# PiCarHat_Master_V4.net
KiCad netlist of a schematic drawn in Altium Designer
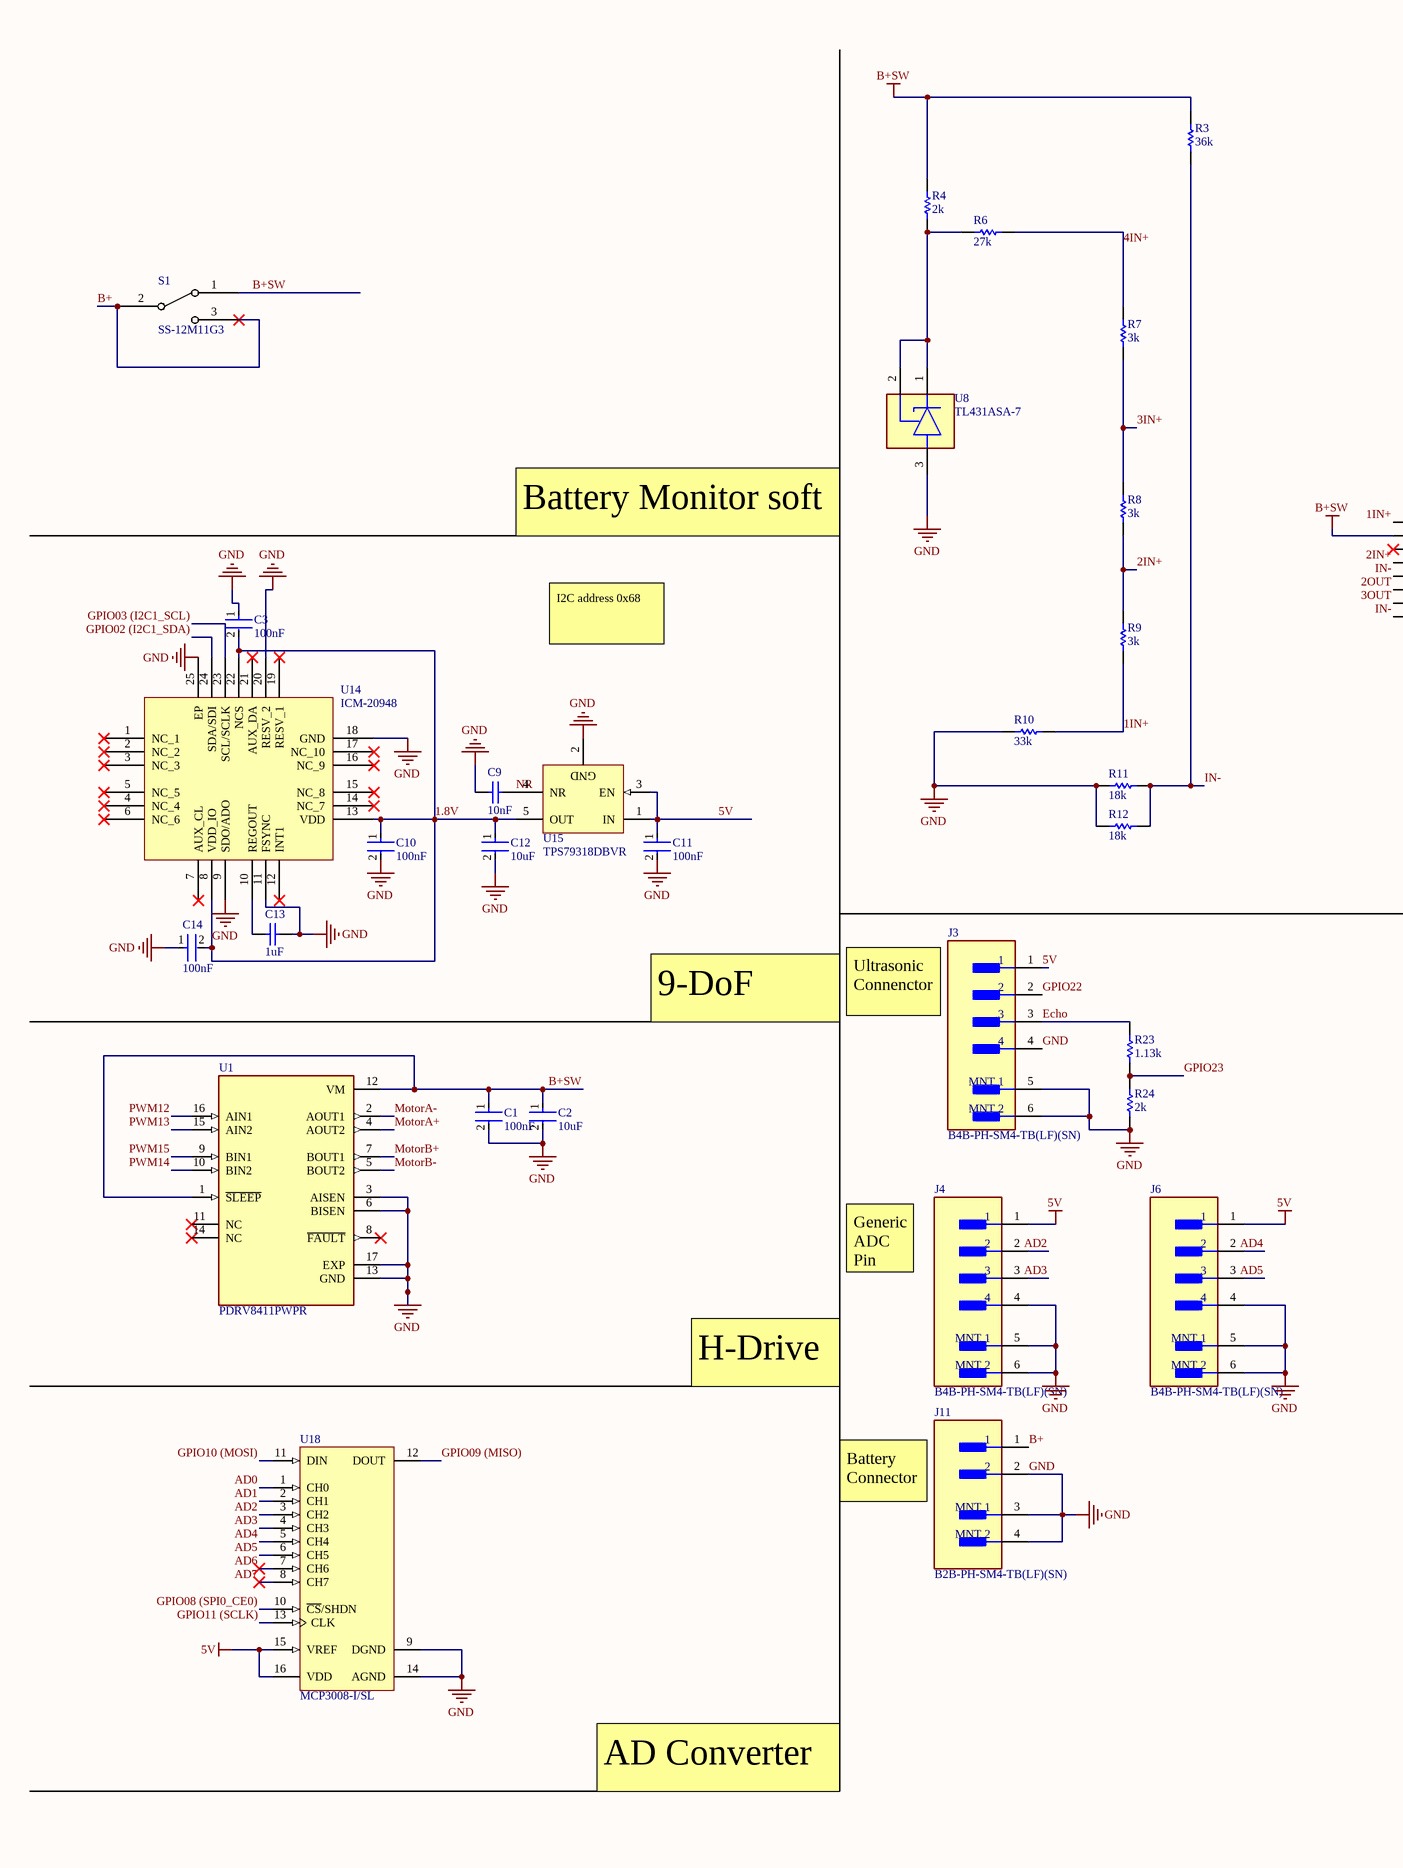
[diagram p0: PiCarHat_Master_V4.SchDoc, left]
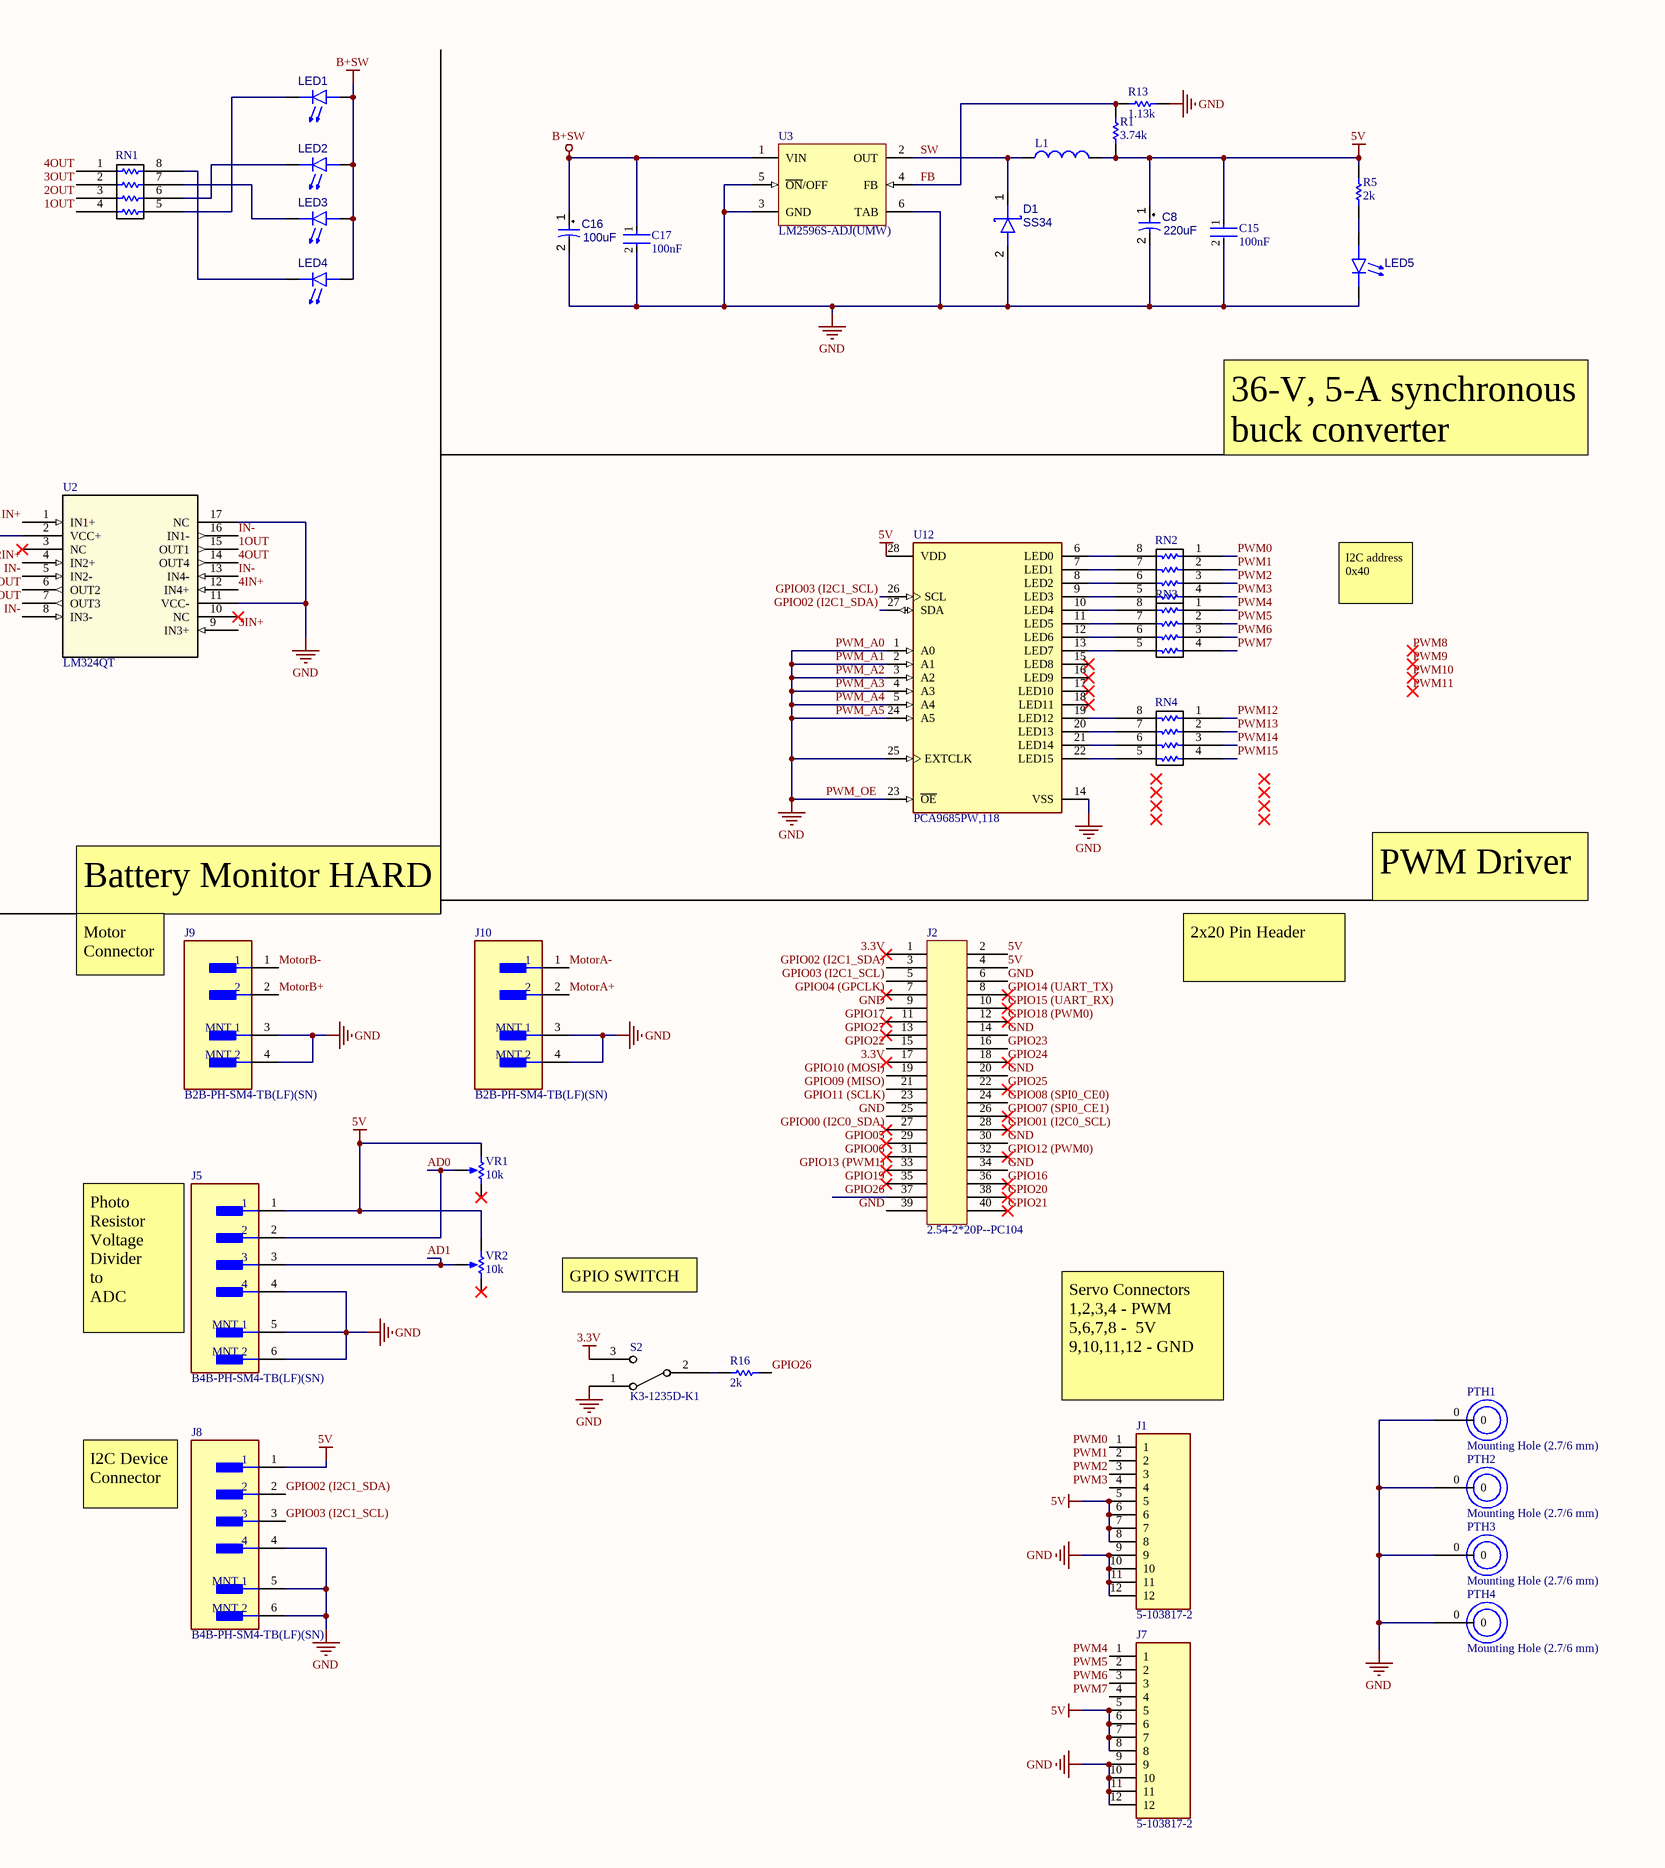
[diagram p1: PiCarHat_Master_V4.SchDoc, right]

(export (version "E")
  (design (tool "Eeschema 10.0.6"))
  (components
    (comp (ref "C1")
      (value "100nF")
      (footprint "FP-CC0805-0_85-IPC_B")
      (description "50V 100nF X7R ±10% 0805 Multilayer Ceramic Capacitors MLCC - SMD/SMT ROHS")
      (fields (field (name "TOLERANCE") "0.1") (field (name "PART NUMBER") "CC0805KRX7R9BB104"))
      (libsource (lib "Altium Content Vault") (part "11868f565c42a9108669ba33697ecf6"))
    )
    (comp (ref "C2")
      (value "10uF")
      (footprint "FP-GRM21B-0_15-MFG")
      (description "25V 10uF X5R ±10% 0805 Multilayer Ceramic Capacitors MLCC - SMD/SMT ROHS")
      (fields (field (name "VOLTAGE") "25V") (field (name "TOLERANCE") "10%"))
      (libsource (lib "Altium Content Vault") (part "b4654b650e69147ec39a6b967a45e02"))
    )
    (comp (ref "C3")
      (value "100nF")
      (footprint "FP-CC0805-0_85-IPC_B")
      (description "50V 100nF X7R ±10% 0805 Multilayer Ceramic Capacitors MLCC - SMD/SMT ROHS")
      (fields (field (name "TOLERANCE") "0.1") (field (name "PART NUMBER") "CC0805KRX7R9BB104"))
      (libsource (lib "Altium Content Vault") (part "11868f565c42a9108669ba33697ecf6"))
    )
    (comp (ref "C8")
      (value "220uF")
      (footprint "RVT1A221M0605-Footprint-1")
      (description "220uF 10V 90mA@120Hz ±20% SMD, D6.3xL5.4mm Aluminum Electrolytic Capacitors - SMD ROHS")
      (fields (field (name "JLCPCB PART #") "C3345") (field (name "PART NUMBER") "RVT1A221M0605"))
      (libsource (lib "Ethan Morton Personal") (part "CAP-NP-2"))
    )
    (comp (ref "C9")
      (value "10nF")
      (footprint "CAPC2013X100X50NL20T25")
      (description "50V 10nF X7R ±10% 0805 Multilayer Ceramic Capacitors MLCC - SMD/SMT ROHS")
      (fields (field (name "PART NUMBER") "C0805F103K5RACTU") (field (name "MANUFACTURER") "Kemet"))
      (libsource (lib "Altium Content Vault") (part "CAP"))
    )
    (comp (ref "C10")
      (value "100nF")
      (footprint "FP-CC0805-0_85-IPC_B")
      (description "50V 100nF X7R ±10% 0805 Multilayer Ceramic Capacitors MLCC - SMD/SMT ROHS")
      (fields (field (name "TOLERANCE") "0.1") (field (name "PART NUMBER") "CC0805KRX7R9BB104"))
      (libsource (lib "Altium Content Vault") (part "11868f565c42a9108669ba33697ecf6"))
    )
    (comp (ref "C11")
      (value "100nF")
      (footprint "FP-CC0805-0_85-IPC_B")
      (description "50V 100nF X7R ±10% 0805 Multilayer Ceramic Capacitors MLCC - SMD/SMT ROHS")
      (fields (field (name "TOLERANCE") "0.1") (field (name "PART NUMBER") "CC0805KRX7R9BB104"))
      (libsource (lib "Altium Content Vault") (part "11868f565c42a9108669ba33697ecf6"))
    )
    (comp (ref "C12")
      (value "10uF")
      (footprint "FP-GRM21B-0_15-MFG")
      (description "25V 10uF X5R ±10% 0805 Multilayer Ceramic Capacitors MLCC - SMD/SMT ROHS")
      (fields (field (name "VOLTAGE") "25V") (field (name "TOLERANCE") "10%"))
      (libsource (lib "Altium Content Vault") (part "b4654b650e69147ec39a6b967a45e02"))
    )
    (comp (ref "C13")
      (value "1uF")
      (footprint "CAPC2013X140X50LL20T25")
      (description "50V 1uF X7R ±10% 0805 Multilayer Ceramic Capacitors MLCC - SMD/SMT ROHS")
      (fields (field (name "PART NUMBER") "C0805C105K3RACTU") (field (name "MANUFACTURER") "Kemet"))
      (libsource (lib "Altium Content Vault") (part "CAP"))
    )
    (comp (ref "C14")
      (value "100nF")
      (footprint "FP-CC0805-0_85-IPC_B")
      (description "50V 100nF X7R ±10% 0805 Multilayer Ceramic Capacitors MLCC - SMD/SMT ROHS")
      (fields (field (name "TOLERANCE") "0.1") (field (name "PART NUMBER") "CC0805KRX7R9BB104"))
      (libsource (lib "Altium Content Vault") (part "11868f565c42a9108669ba33697ecf6"))
    )
    (comp (ref "C15")
      (value "100nF")
      (footprint "FP-CC0805-0_85-IPC_B")
      (description "50V 100nF X7R ±10% 0805 Multilayer Ceramic Capacitors MLCC - SMD/SMT ROHS")
      (fields (field (name "TOLERANCE") "0.1") (field (name "PART NUMBER") "CC0805KRX7R9BB104"))
      (libsource (lib "Altium Content Vault") (part "11868f565c42a9108669ba33697ecf6"))
    )
    (comp (ref "C16")
      (value "100uF")
      (footprint "RVT1C101M0605-Footprint-1")
      (description "100uF 16V 63mA@120Hz ±20% SMD, D6.3xL5.4mm Aluminum Electrolytic Capacitors - SMD ROHS")
      (fields (field (name "PART NUMBER") "RVT1C101M0605") (field (name "JLCPCB PART #") "C37308"))
      (libsource (lib "Ethan Morton Personal") (part "Copy of CAP-NP-2"))
    )
    (comp (ref "C17")
      (value "100nF")
      (footprint "FP-CC0805-0_85-IPC_B")
      (description "50V 100nF X7R ±10% 0805 Multilayer Ceramic Capacitors MLCC - SMD/SMT ROHS")
      (fields (field (name "TOLERANCE") "0.1") (field (name "PART NUMBER") "CC0805KRX7R9BB104"))
      (libsource (lib "Altium Content Vault") (part "11868f565c42a9108669ba33697ecf6"))
    )
    (comp (ref "D1")
      (value "SS34")
      (footprint "SS34-Footprint-1")
      (description "40V Independent Type 3A 550mV@3A SMA(DO-214AC) Schottky Diodes ROHS")
      (fields (field (name "JLCPCB PART #") "C8678"))
      (libsource (lib "Ethan Morton Personal") (part "Copy of DIODE-2"))
    )
    (comp (ref "J1")
      (value "5-103817-2")
      (footprint "TE_5-103817-2")
      (fields
        (field (name "MF") "TE Connectivity")
        (field (name "PART NUMBER") "TSW-104-07-L-T")
        (field (name "JLCPCB PART #") "C32713291")
      )
      (libsource (lib "Ethan Morton Personal") (part "5-103817-2"))
    )
    (comp (ref "J2")
      (value "2.54-2*20P--PC104")
      (footprint "New footprint 1")
      (description "2.54mm 2.54mm Double Row 40P Brass Direct Insert 2x20P Plugin,P=2.54mm Female Headers ROHS")
      (fields (field (name "PART NUMBER") "2.54-2*20P母长PC104") (field (name "JLCPCB PART #") "C35165"))
      (libsource (lib "Ethan Morton Personal") (part "2x20 GPIO Header"))
    )
    (comp (ref "J3")
      (value "B4B-PH-SM4-TB(LF)(SN)")
      (footprint "FP-B4B-PH-SM4-TB-MFG")
      (description "2.0mm pitch/Disconnectable Insulation displacement and Crimp style connectors")
      (fields (field (name "JLCPCB PART #") "C160354"))
      (libsource (lib "Ethan Morton Personal") (part "f4320a1371cd6270e33bce1916c33c0"))
    )
    (comp (ref "J4")
      (value "B4B-PH-SM4-TB(LF)(SN)")
      (footprint "FP-B4B-PH-SM4-TB-MFG")
      (description "2.0mm pitch/Disconnectable Insulation displacement and Crimp style connectors")
      (fields (field (name "JLCPCB PART #") "C160354"))
      (libsource (lib "Ethan Morton Personal") (part "f4320a1371cd6270e33bce1916c33c0"))
    )
    (comp (ref "J5")
      (value "B4B-PH-SM4-TB(LF)(SN)")
      (footprint "FP-B4B-PH-SM4-TB-MFG")
      (description "2.0mm pitch/Disconnectable Insulation displacement and Crimp style connectors")
      (fields (field (name "JLCPCB PART #") "C160354"))
      (libsource (lib "Ethan Morton Personal") (part "f4320a1371cd6270e33bce1916c33c0"))
    )
    (comp (ref "J6")
      (value "B4B-PH-SM4-TB(LF)(SN)")
      (footprint "FP-B4B-PH-SM4-TB-MFG")
      (description "2.0mm pitch/Disconnectable Insulation displacement and Crimp style connectors")
      (fields (field (name "JLCPCB PART #") "C160354"))
      (libsource (lib "Ethan Morton Personal") (part "f4320a1371cd6270e33bce1916c33c0"))
    )
    (comp (ref "J7")
      (value "5-103817-2")
      (footprint "TE_5-103817-2")
      (fields
        (field (name "PART NUMBER") "TSW-104-07-L-T")
        (field (name "MF") "TE Connectivity")
        (field (name "JLCPCB PART #") "C32713291")
      )
      (libsource (lib "Ethan Morton Personal") (part "5-103817-2"))
    )
    (comp (ref "J8")
      (value "B4B-PH-SM4-TB(LF)(SN)")
      (footprint "FP-B4B-PH-SM4-TB-MFG")
      (description "2.0mm pitch/Disconnectable Insulation displacement and Crimp style connectors")
      (fields (field (name "JLCPCB PART #") "C160354"))
      (libsource (lib "Ethan Morton Personal") (part "f4320a1371cd6270e33bce1916c33c0"))
    )
    (comp (ref "J9")
      (value "B2B-PH-SM4-TB(LF)(SN)")
      (footprint "FP-B2B-PH-SM4-TB_LF_SN-MFG")
      (fields (field (name "PART NUMBER") "B2B-PH-SM4-TB") (field (name "JLCPCB PART #") "C160352"))
      (libsource (lib "Ethan Morton Personal") (part "56ec3178a87b3978bdc1b3682cd516a"))
    )
    (comp (ref "J10")
      (value "B2B-PH-SM4-TB(LF)(SN)")
      (footprint "FP-B2B-PH-SM4-TB_LF_SN-MFG")
      (fields (field (name "PART NUMBER") "B2B-PH-SM4-TB") (field (name "JLCPCB PART #") "C160352"))
      (libsource (lib "Ethan Morton Personal") (part "56ec3178a87b3978bdc1b3682cd516a"))
    )
    (comp (ref "J11")
      (value "B2B-PH-SM4-TB(LF)(SN)")
      (footprint "FP-B2B-PH-SM4-TB_LF_SN-MFG")
      (fields (field (name "PART NUMBER") "B2B-PH-SM4-TB") (field (name "JLCPCB PART #") "C160352"))
      (libsource (lib "Ethan Morton Personal") (part "56ec3178a87b3978bdc1b3682cd516a"))
    )
    (comp (ref "L1")
      (value "FXL1050-470-M")
      (footprint "FXL1050-470-M-Footprint-1")
      (description "3.7A 47uH Integrated molded inductor ±20% 4.5A SMD,10x11.5mm Power Inductors ROHS")
      (fields (field (name "JLCPCB PART #") "C5359268"))
      (libsource (lib "Ethan Morton Personal") (part "IND-2"))
    )
    (comp (ref "LED1")
      (value "KT-0603R")
      (footprint "XL-1608SURC-06-Footprint-1")
      (description "-40℃~+85℃ Red 0603 LED Indication - Discrete ROHS")
      (fields (field (name "JLCPCB PART #") "C2286"))
      (libsource (lib "Ethan Morton Personal") (part "Copy of DIODE-LED-2"))
    )
    (comp (ref "LED2")
      (value "KT-0603R")
      (footprint "XL-1608SURC-06-Footprint-1")
      (description "-40℃~+85℃ Red 0603 LED Indication - Discrete ROHS")
      (fields (field (name "JLCPCB PART #") "C2286"))
      (libsource (lib "Ethan Morton Personal") (part "Copy of DIODE-LED-2"))
    )
    (comp (ref "LED3")
      (value "KT-0603R")
      (footprint "XL-1608SURC-06-Footprint-1")
      (description "-40℃~+85℃ Red 0603 LED Indication - Discrete ROHS")
      (fields (field (name "JLCPCB PART #") "C2286"))
      (libsource (lib "Ethan Morton Personal") (part "Copy of DIODE-LED-2"))
    )
    (comp (ref "LED4")
      (value "KT-0603R")
      (footprint "XL-1608SURC-06-Footprint-1")
      (description "-40℃~+85℃ Red 0603 LED Indication - Discrete ROHS")
      (fields (field (name "JLCPCB PART #") "C2286"))
      (libsource (lib "Ethan Morton Personal") (part "Copy of DIODE-LED-2"))
    )
    (comp (ref "LED5")
      (value "KT-0603R")
      (footprint "XL-1608SURC-06-Footprint-1")
      (description "-40℃~+85℃ Red 0603 LED Indication - Discrete ROHS")
      (fields (field (name "JLCPCB PART #") "C2286"))
      (libsource (lib "Ethan Morton Personal") (part "Copy of DIODE-LED-2"))
    )
    (comp (ref "PTH1")
      (value "Mounting Hole (2.7/6 mm)")
      (footprint "New footprint 1")
      (description "DO NOT PLACE")
      (libsource (lib "Ethan Morton Personal") (part "Mounting Hole (2.7/6 mm)"))
    )
    (comp (ref "PTH2")
      (value "Mounting Hole (2.7/6 mm)")
      (footprint "New footprint 1")
      (description "DO NOT PLACE")
      (libsource (lib "Ethan Morton Personal") (part "Mounting Hole (2.7/6 mm)"))
    )
    (comp (ref "PTH3")
      (value "Mounting Hole (2.7/6 mm)")
      (footprint "New footprint 1")
      (description "DO NOT PLACE")
      (libsource (lib "Ethan Morton Personal") (part "Mounting Hole (2.7/6 mm)"))
    )
    (comp (ref "PTH4")
      (value "Mounting Hole (2.7/6 mm)")
      (footprint "New footprint 1")
      (description "DO NOT PLACE")
      (libsource (lib "Ethan Morton Personal") (part "Mounting Hole (2.7/6 mm)"))
    )
    (comp (ref "R1")
      (value "3.74k")
      (footprint "RESC1608X55X30LL15T15")
      (description "100mW Thick Film Resistors 75V ±100ppm/℃ ±1% 3.74kΩ 0603 Chip Resistor - Surface Mount ROHS")
      (fields (field (name "PART NUMBER") "ERJ-3EKF3741V") (field (name "MANUFACTURER") "Panasonic"))
      (libsource (lib "Altium Content Vault") (part "RES"))
    )
    (comp (ref "R3")
      (value "36k")
      (footprint "RESC1608X55X30LL20T20")
      (description "100mW Thick Film Resistors 75V ±100ppm/℃ ±1% 36kΩ 0603 Chip Resistor - Surface Mount ROHS")
      (fields (field (name "MANUFACTURER") "Panasonic") (field (name "PART NUMBER") "ERA3AEB363V"))
      (libsource (lib "Altium Content Vault") (part "RES"))
    )
    (comp (ref "R4")
      (value "2k")
      (footprint "RESC1608X55X25LL10T15")
      (description "100mW Thick Film Resistors 75V ±100ppm/℃ ±1% 2kΩ 0603 Chip Resistor - Surface Mount ROHS")
      (fields (field (name "TOLERANCE") "±1%") (field (name "MANUFACTURER") "Yageo"))
      (libsource (lib "") (part "RES-2_1"))
    )
    (comp (ref "R5")
      (value "2k")
      (footprint "RESC1608X55X25LL10T15")
      (description "100mW Thick Film Resistors 75V ±100ppm/℃ ±1% 2kΩ 0603 Chip Resistor - Surface Mount ROHS")
      (fields (field (name "TOLERANCE") "±1%") (field (name "MANUFACTURER") "Yageo"))
      (libsource (lib "") (part "RES-2_1"))
    )
    (comp (ref "R6")
      (value "27k")
      (footprint "RESC1608X55X25LL10T15")
      (description "100mW Thick Film Resistors 75V ±100ppm/℃ ±1% 27kΩ 0603 Chip Resistor - Surface Mount ROHS")
      (fields (field (name "MANUFACTURER") "Yageo") (field (name "TOLERANCE") "1%"))
      (libsource (lib "") (part "RES-2_1"))
    )
    (comp (ref "R7")
      (value "3k")
      (footprint "RESC1608X55X25LL10T15")
      (description "100mW Thick Film Resistors 75V ±100ppm/℃ ±1% 3kΩ 0603 Chip Resistor - Surface Mount ROHS")
      (fields (field (name "MANUFACTURER") "Yageo") (field (name "PART NUMBER") "RC0603FR-073KL"))
      (libsource (lib "Altium Content Vault") (part "RES"))
    )
    (comp (ref "R8")
      (value "3k")
      (footprint "RESC1608X55X25LL10T15")
      (description "100mW Thick Film Resistors 75V ±100ppm/℃ ±1% 3kΩ 0603 Chip Resistor - Surface Mount ROHS")
      (fields (field (name "MANUFACTURER") "Yageo") (field (name "PART NUMBER") "RC0603FR-073KL"))
      (libsource (lib "Altium Content Vault") (part "RES"))
    )
    (comp (ref "R9")
      (value "3k")
      (footprint "RESC1608X55X25LL10T15")
      (description "100mW Thick Film Resistors 75V ±100ppm/℃ ±1% 3kΩ 0603 Chip Resistor - Surface Mount ROHS")
      (fields (field (name "MANUFACTURER") "Yageo") (field (name "PART NUMBER") "RC0603FR-073KL"))
      (libsource (lib "Altium Content Vault") (part "RES"))
    )
    (comp (ref "R10")
      (value "33k")
      (footprint "RESC1608X55X25LL10T15")
      (description "100mW Thick Film Resistors 75V ±100ppm/℃ ±1% 33kΩ 0603 Chip Resistor - Surface Mount ROHS")
      (fields (field (name "TOLERANCE") "1%") (field (name "MANUFACTURER") "Yageo"))
      (libsource (lib "") (part "RES-2_1"))
    )
    (comp (ref "R11")
      (value "18k")
      (footprint "RESC1608X55X30LL15T15")
      (description "100mW Thick Film Resistors 75V ±100ppm/℃ ±1% 18kΩ 0603 Chip Resistor - Surface Mount ROHS")
      (fields (field (name "MANUFACTURER") "Panasonic") (field (name "PART NUMBER") "ERJ3EKF1802V"))
      (libsource (lib "Altium Content Vault") (part "RES-2"))
    )
    (comp (ref "R12")
      (value "18k")
      (footprint "RESC1608X55X30LL15T15")
      (description "100mW Thick Film Resistors 75V ±100ppm/℃ ±1% 18kΩ 0603 Chip Resistor - Surface Mount ROHS")
      (fields (field (name "MANUFACTURER") "Panasonic") (field (name "PART NUMBER") "ERJ3EKF1802V"))
      (libsource (lib "Altium Content Vault") (part "RES-2"))
    )
    (comp (ref "R13")
      (value "1.13k")
      (footprint "RESC1609X50X30LL10T20")
      (description "100mW Thick Film Resistors 75V ±100ppm/℃ ±1% 1.13kΩ 0603 Chip Resistor - Surface Mount ROHS")
      (fields (field (name "PART NUMBER") "CRCW06031K13FKEA") (field (name "MANUFACTURER") "Vishay Dale"))
      (libsource (lib "Altium Content Vault") (part "RES"))
    )
    (comp (ref "R16")
      (value "2k")
      (footprint "RESC1608X55X25LL10T15")
      (description "100mW Thick Film Resistors 75V ±100ppm/℃ ±1% 2kΩ 0603 Chip Resistor - Surface Mount ROHS")
      (fields (field (name "TOLERANCE") "±1%") (field (name "MANUFACTURER") "Yageo"))
      (libsource (lib "") (part "RES-2_1"))
    )
    (comp (ref "R23")
      (value "1.13k")
      (footprint "RESC1609X50X30LL10T20")
      (description "100mW Thick Film Resistors 75V ±100ppm/℃ ±1% 1.13kΩ 0603 Chip Resistor - Surface Mount ROHS")
      (fields (field (name "PART NUMBER") "CRCW06031K13FKEA") (field (name "MANUFACTURER") "Vishay Dale"))
      (libsource (lib "Altium Content Vault") (part "RES"))
    )
    (comp (ref "R24")
      (value "2k")
      (footprint "RESC1608X55X25LL10T15")
      (description "100mW Thick Film Resistors 75V ±100ppm/℃ ±1% 2kΩ 0603 Chip Resistor - Surface Mount ROHS")
      (fields (field (name "TOLERANCE") "±1%") (field (name "MANUFACTURER") "Yageo"))
      (libsource (lib "") (part "RES-2_1"))
    )
    (comp (ref "RN1")
      (value "4D03WGJ0103T5E")
      (footprint "4D03WGJ0103T5E-Footprint-1")
      (description "4 ±5% 10kΩ 62.5mW ±200ppm/℃ 0603x4 Resistor Networks, Arrays ROHS")
      (fields (field (name "JLCPCB PART #") "C29718"))
      (libsource (lib "Ethan Morton Personal") (part "10k Resistor Network"))
    )
    (comp (ref "RN2")
      (value "4D03WGJ0101T5E")
      (footprint "4D03WGJ0101T5E-Footprint-1")
      (description "4 ±5% 100Ω 62.5mW ±200ppm/℃ 0603x4 Resistor Networks, Arrays ROHS")
      (fields (field (name "JLCPCB PART #") "C25506"))
      (libsource (lib "Ethan Morton Personal") (part "4D03WGJ0101T5E-Symbol-1"))
    )
    (comp (ref "RN3")
      (value "4D03WGJ0101T5E")
      (footprint "4D03WGJ0101T5E-Footprint-1")
      (description "4 ±5% 100Ω 62.5mW ±200ppm/℃ 0603x4 Resistor Networks, Arrays ROHS")
      (fields (field (name "JLCPCB PART #") "C25506"))
      (libsource (lib "Ethan Morton Personal") (part "4D03WGJ0101T5E-Symbol-1"))
    )
    (comp (ref "RN4")
      (value "4D03WGJ0101T5E")
      (footprint "4D03WGJ0101T5E-Footprint-1")
      (description "4 ±5% 100Ω 62.5mW ±200ppm/℃ 0603x4 Resistor Networks, Arrays ROHS")
      (fields (field (name "JLCPCB PART #") "C25506"))
      (libsource (lib "Ethan Morton Personal") (part "4D03WGJ0101T5E-Symbol-1"))
    )
    (comp (ref "S1")
      (value "SS-12M11G3")
      (footprint "SS-12M11G5-Footprint-1")
      (fields (field (name "JLCPCB PART #") "C2879832"))
      (libsource (lib "Ethan Morton Personal") (part "SS-12M11G5-Symbol-1"))
    )
    (comp (ref "S2")
      (value "K3-1235D-K1")
      (footprint "K3-1235D-K1-Footprint-1")
      (fields (field (name "JLCPCB PART #") "C145860"))
      (libsource (lib "Ethan Morton Personal") (part "K3-1235D-K1-Symbol-1"))
    )
    (comp (ref "U1")
      (value "PDRV8411PWPR")
      (footprint "PWP0016C-IPC_B")
      (description "1.65-V to 11-V, 4-A, dual H-bridge motor driver with current regulation 16-HTSSOP -40 to 125")
      (fields (field (name "JLCPCB PART #") "C18212622"))
      (libsource (lib "Ethan Morton Personal") (part "PDRV8411PWPR-Symbol-1"))
    )
    (comp (ref "U2")
      (value "LM324QT")
      (footprint "LM324QT-Footprint-1")
      (description "Operational Amplifier, 4 Func, 9000uV Offset-Max, BIPolar, PQCC16")
      (fields (field (name "JLCPCB PART #") "C183029"))
      (libsource (lib "Ethan Morton Personal") (part "LM324QT-Symbol-1"))
    )
    (comp (ref "U3")
      (value "LM2596S-ADJ(UMW)")
      (footprint "TS5B_L")
      (description "Step-down type Adjustable 40V 1.2V~37V 3A TO-263-5 DC-DC Converters ROHS")
      (fields (field (name "MANUFACTURER") "National Semiconductor") (field (name "JLCPCB PART #") "C347423"))
      (libsource (lib "Altium Content Vault") (part "PM-REG-LM2575HVS-12"))
    )
    (comp (ref "U8")
      (value "TL431ASA-7")
      (footprint "FP-SOT23-MFG")
      (description "2.495V~36V ±1% 100mA Adjustable SOT-23 Voltage Reference ROHS")
      (fields
        (field (name "OCTOPART") "https://octopart.com/tl431asa-7-diodes+inc.-18832779")
        (field (name "MANUFACTURER") "DIODES INC.")
      )
      (libsource (lib "Altium Content Vault") (part "bb7a1bf3cd7629b94a2ffd22ed0b9f9"))
    )
    (comp (ref "U12")
      (value "PCA9685PW,118")
      (footprint "FP-SOT361-1-IPC_B")
      (description "IC LED DRIVER RGBA 28-TSSOP")
      (fields
        (field (name "MANUFACTURER") "NXP Semiconductors")
        (field (name "OCTOPART") "https://octopart.com/pca9685pw%2C118-nxp+semiconductors-11853435")
      )
      (libsource (lib "Altium Content Vault") (part "50b6f6febb80a1ca83d1eae7256368c"))
    )
    (comp (ref "U14")
      (value "ICM-20948")
      (footprint "TDK-QFN-24_L")
      (description "Accelerometer and Gyroscope Compass 9-Axis Digital 24-Pin QFN T/R")
      (fields (field (name "JLCPCB PART #") "C726001"))
      (libsource (lib "Ethan Morton Personal") (part "ICM-20948-Symbol-1"))
    )
    (comp (ref "U15")
      (value "TPS79318DBVR")
      (footprint "DBV0005A_M")
      (fields (field (name "MANUFACTURER") "Texas Instruments") (field (name "JLCPCB PART #") "C7102"))
      (libsource (lib "Altium Content Vault") (part "TI-TPS79NXX-YYSOT5"))
    )
    (comp (ref "U18")
      (value "MCP3008-I/SL")
      (footprint "SOIC-SL16_L")
      (libsource (lib "Altium Content Vault") (part "CON-ADC-MCP3008-16"))
    )
    (comp (ref "VR1")
      (value "10k")
      (footprint "BOUR-3362P")
      (description "±10% ±100ppm/℃ 500mW 10kΩ Plugin-3P,7x6.6mm Potentiometers, Variable Resistors ROHS")
      (fields (field (name "TOLERANCE") "10%") (field (name "POWER") "500mW"))
      (libsource (lib "Ethan Morton Personal") (part "RES-POT-3"))
    )
    (comp (ref "VR2")
      (value "10k")
      (footprint "BOUR-3362P")
      (description "±10% ±100ppm/℃ 500mW 10kΩ Plugin-3P,7x6.6mm Potentiometers, Variable Resistors ROHS")
      (fields (field (name "TOLERANCE") "10%") (field (name "POWER") "500mW"))
      (libsource (lib "Ethan Morton Personal") (part "RES-POT-3"))
    )
  )
  (nets
    (net (code "1") (name "/1.8V") (class "Default")
      (node (ref "C10") (pin "1") (pinfunction "1_1") (pintype "passive"))
      (node (ref "C12") (pin "1") (pinfunction "1_1") (pintype "passive"))
      (node (ref "C14") (pin "2") (pinfunction "2_2") (pintype "passive"))
      (node (ref "C3") (pin "2") (pinfunction "2_2") (pintype "passive"))
      (node (ref "U14") (pin "13") (pinfunction "VDD_13") (pintype "passive"))
      (node (ref "U14") (pin "22") (pinfunction "NCS_22") (pintype "passive"))
      (node (ref "U14") (pin "8") (pinfunction "VDD_IO_8") (pintype "passive"))
      (node (ref "U15") (pin "5") (pinfunction "OUT_5") (pintype "power_in"))
    )
    (net (code "2") (name "/1IN+") (class "Default")
      (node (ref "R10") (pin "2") (pinfunction "2_2") (pintype "passive"))
      (node (ref "R9") (pin "2") (pinfunction "2_2") (pintype "passive"))
      (node (ref "U2") (pin "1") (pinfunction "IN1+_1") (pintype "input"))
    )
    (net (code "3") (name "/1OUT") (class "Default")
      (node (ref "RN1") (pin "4") (pinfunction "4_4") (pintype "passive"))
      (node (ref "U2") (pin "15") (pinfunction "OUT1_15") (pintype "output"))
    )
    (net (code "4") (name "/2IN+") (class "Default")
      (node (ref "R8") (pin "2") (pinfunction "2_2") (pintype "passive"))
      (node (ref "R9") (pin "1") (pinfunction "1_1") (pintype "passive"))
      (node (ref "U2") (pin "4") (pinfunction "IN2+_4") (pintype "input"))
    )
    (net (code "5") (name "/2OUT") (class "Default")
      (node (ref "RN1") (pin "3") (pinfunction "3_3") (pintype "passive"))
      (node (ref "U2") (pin "6") (pinfunction "OUT2_6") (pintype "output"))
    )
    (net (code "6") (name "/3IN+") (class "Default")
      (node (ref "R7") (pin "2") (pinfunction "2_2") (pintype "passive"))
      (node (ref "R8") (pin "1") (pinfunction "1_1") (pintype "passive"))
      (node (ref "U2") (pin "9") (pinfunction "IN3+_9") (pintype "input"))
    )
    (net (code "7") (name "/3OUT") (class "Default")
      (node (ref "RN1") (pin "2") (pinfunction "2_2") (pintype "passive"))
      (node (ref "U2") (pin "7") (pinfunction "OUT3_7") (pintype "output"))
    )
    (net (code "8") (name "/4IN+") (class "Default")
      (node (ref "R6") (pin "2") (pinfunction "2_2") (pintype "passive"))
      (node (ref "R7") (pin "1") (pinfunction "1_1") (pintype "passive"))
      (node (ref "U2") (pin "12") (pinfunction "IN4+_12") (pintype "input"))
    )
    (net (code "9") (name "/4OUT") (class "Default")
      (node (ref "RN1") (pin "1") (pinfunction "6_1") (pintype "passive"))
      (node (ref "U2") (pin "14") (pinfunction "OUT4_14") (pintype "output"))
    )
    (net (code "10") (name "/AD0") (class "Default")
      (node (ref "J5") (pin "2") (pinfunction "2_2") (pintype "passive"))
      (node (ref "U18") (pin "1") (pinfunction "CH0_1") (pintype "input"))
      (node (ref "VR1") (pin "2") (pinfunction "S_2") (pintype "passive"))
    )
    (net (code "11") (name "/AD1") (class "Default")
      (node (ref "J5") (pin "3") (pinfunction "3_3") (pintype "passive"))
      (node (ref "U18") (pin "2") (pinfunction "CH1_2") (pintype "input"))
      (node (ref "VR2") (pin "2") (pinfunction "S_2") (pintype "passive"))
    )
    (net (code "12") (name "/AD2") (class "Default")
      (node (ref "J4") (pin "2") (pinfunction "2_2") (pintype "passive"))
      (node (ref "U18") (pin "3") (pinfunction "CH2_3") (pintype "input"))
    )
    (net (code "13") (name "/AD3") (class "Default")
      (node (ref "J4") (pin "3") (pinfunction "3_3") (pintype "passive"))
      (node (ref "U18") (pin "4") (pinfunction "CH3_4") (pintype "input"))
    )
    (net (code "14") (name "/AD4") (class "Default")
      (node (ref "J6") (pin "2") (pinfunction "2_2") (pintype "passive"))
      (node (ref "U18") (pin "5") (pinfunction "CH4_5") (pintype "input"))
    )
    (net (code "15") (name "/AD5") (class "Default")
      (node (ref "J6") (pin "3") (pinfunction "3_3") (pintype "passive"))
      (node (ref "U18") (pin "6") (pinfunction "CH5_6") (pintype "input"))
    )
    (net (code "16") (name "/AD6") (class "Default")
      (node (ref "U18") (pin "7") (pinfunction "CH6_7") (pintype "input+no_connect"))
    )
    (net (code "17") (name "/AD7") (class "Default")
      (node (ref "U18") (pin "8") (pinfunction "CH7_8") (pintype "input+no_connect"))
    )
    (net (code "18") (name "/B+") (class "Default")
      (node (ref "J11") (pin "1") (pinfunction "1_1") (pintype "passive"))
      (node (ref "S1") (pin "2") (pinfunction "2_2") (pintype "passive"))
      (node (ref "S1") (pin "3") (pinfunction "3_3") (pintype "passive"))
    )
    (net (code "19") (name "/Echo") (class "Default")
      (node (ref "J3") (pin "3") (pinfunction "3_3") (pintype "passive"))
      (node (ref "R23") (pin "2") (pinfunction "2_2") (pintype "passive"))
    )
    (net (code "20") (name "/FB") (class "Default")
      (node (ref "R1") (pin "2") (pinfunction "2_2") (pintype "passive"))
      (node (ref "R13") (pin "1") (pinfunction "1_1") (pintype "passive"))
      (node (ref "U3") (pin "4") (pinfunction "FB_4") (pintype "input"))
    )
    (net (code "21") (name "/GPIO00 (I2C0_SDA)") (class "Default")
      (node (ref "J2") (pin "27") (pintype "passive+no_connect"))
    )
    (net (code "22") (name "/GPIO01 (I2C0_SCL)") (class "Default")
      (node (ref "J2") (pin "28") (pintype "passive+no_connect"))
    )
    (net (code "23") (name "/GPIO02 (I2C1_SDA)") (class "Default")
      (node (ref "J2") (pin "3") (pintype "passive"))
      (node (ref "J8") (pin "2") (pinfunction "2_2") (pintype "passive"))
      (node (ref "U12") (pin "27") (pinfunction "SDA_27") (pintype "bidirectional"))
      (node (ref "U14") (pin "24") (pinfunction "SDA/SDI_24") (pintype "passive"))
    )
    (net (code "24") (name "/GPIO03 (I2C1_SCL)") (class "Default")
      (node (ref "J2") (pin "5") (pintype "passive"))
      (node (ref "J8") (pin "3") (pinfunction "3_3") (pintype "passive"))
      (node (ref "U12") (pin "26") (pinfunction "SCL_26") (pintype "input"))
      (node (ref "U14") (pin "23") (pinfunction "SCL/SCLK_23") (pintype "passive"))
    )
    (net (code "25") (name "/GPIO04 (GPCLK)") (class "Default")
      (node (ref "J2") (pin "7") (pintype "passive+no_connect"))
    )
    (net (code "26") (name "/GPIO05") (class "Default")
      (node (ref "J2") (pin "29") (pintype "passive+no_connect"))
    )
    (net (code "27") (name "/GPIO06") (class "Default")
      (node (ref "J2") (pin "31") (pintype "passive+no_connect"))
    )
    (net (code "28") (name "/GPIO07 (SPI0_CE1)") (class "Default")
      (node (ref "J2") (pin "26") (pintype "passive+no_connect"))
    )
    (net (code "29") (name "/GPIO08 (SPI0_CE0)") (class "Default")
      (node (ref "J2") (pin "24") (pintype "passive"))
      (node (ref "U18") (pin "10") (pinfunction "~{CS}/SHDN_10") (pintype "input"))
    )
    (net (code "30") (name "/GPIO09 (MISO)") (class "Default")
      (node (ref "J2") (pin "21") (pintype "passive"))
      (node (ref "U18") (pin "12") (pinfunction "DOUT_12") (pintype "tri_state"))
    )
    (net (code "31") (name "/GPIO10 (MOSI)") (class "Default")
      (node (ref "J2") (pin "19") (pintype "passive"))
      (node (ref "U18") (pin "11") (pinfunction "DIN_11") (pintype "input"))
    )
    (net (code "32") (name "/GPIO11 (SCLK)") (class "Default")
      (node (ref "J2") (pin "23") (pintype "passive"))
      (node (ref "U18") (pin "13") (pinfunction "CLK_13") (pintype "input"))
    )
    (net (code "33") (name "/GPIO12 (PWM0)") (class "Default")
      (node (ref "J2") (pin "32") (pintype "passive+no_connect"))
    )
    (net (code "34") (name "/GPIO13 (PWM1)") (class "Default")
      (node (ref "J2") (pin "33") (pintype "passive+no_connect"))
    )
    (net (code "35") (name "/GPIO14 (UART_TX)") (class "Default")
      (node (ref "J2") (pin "8") (pintype "passive+no_connect"))
    )
    (net (code "36") (name "/GPIO15 (UART_RX)") (class "Default")
      (node (ref "J2") (pin "10") (pintype "passive+no_connect"))
    )
    (net (code "37") (name "/GPIO16") (class "Default")
      (node (ref "J2") (pin "36") (pintype "passive+no_connect"))
    )
    (net (code "38") (name "/GPIO17") (class "Default")
      (node (ref "J2") (pin "11") (pintype "passive+no_connect"))
    )
    (net (code "39") (name "/GPIO18 (PWM0)") (class "Default")
      (node (ref "J2") (pin "12") (pintype "passive+no_connect"))
    )
    (net (code "40") (name "/GPIO19") (class "Default")
      (node (ref "J2") (pin "35") (pintype "passive+no_connect"))
    )
    (net (code "41") (name "/GPIO20") (class "Default")
      (node (ref "J2") (pin "38") (pintype "passive+no_connect"))
    )
    (net (code "42") (name "/GPIO21") (class "Default")
      (node (ref "J2") (pin "40") (pintype "passive+no_connect"))
    )
    (net (code "43") (name "/GPIO22") (class "Default")
      (node (ref "J2") (pin "15") (pintype "passive"))
      (node (ref "J3") (pin "2") (pinfunction "2_2") (pintype "passive"))
    )
    (net (code "44") (name "/GPIO23") (class "Default")
      (node (ref "J2") (pin "16") (pintype "passive"))
      (node (ref "R23") (pin "1") (pinfunction "1_1") (pintype "passive"))
      (node (ref "R24") (pin "2") (pinfunction "2_2") (pintype "passive"))
    )
    (net (code "45") (name "/GPIO24") (class "Default")
      (node (ref "J2") (pin "18") (pintype "passive+no_connect"))
    )
    (net (code "46") (name "/GPIO25") (class "Default")
      (node (ref "J2") (pin "22") (pintype "passive+no_connect"))
    )
    (net (code "47") (name "/GPIO26") (class "Default")
      (node (ref "J2") (pin "37") (pintype "passive"))
      (node (ref "R16") (pin "1") (pinfunction "1_1") (pintype "passive"))
    )
    (net (code "48") (name "/GPIO27") (class "Default")
      (node (ref "J2") (pin "13") (pintype "passive+no_connect"))
    )
    (net (code "49") (name "/IN-") (class "Default")
      (node (ref "R11") (pin "2") (pinfunction "2_2") (pintype "passive"))
      (node (ref "R12") (pin "2") (pinfunction "2_2") (pintype "passive"))
      (node (ref "R3") (pin "1") (pinfunction "1_1") (pintype "passive"))
      (node (ref "U2") (pin "13") (pinfunction "IN4-_13") (pintype "input"))
      (node (ref "U2") (pin "16") (pinfunction "IN1-_16") (pintype "output"))
      (node (ref "U2") (pin "5") (pinfunction "IN2-_5") (pintype "input"))
      (node (ref "U2") (pin "8") (pinfunction "IN3-_8") (pintype "input"))
    )
    (net (code "50") (name "/MotorA+") (class "Default")
      (node (ref "J10") (pin "2") (pinfunction "2_2") (pintype "passive"))
      (node (ref "U1") (pin "4") (pinfunction "AOUT2_4") (pintype "output"))
    )
    (net (code "51") (name "/MotorA-") (class "Default")
      (node (ref "J10") (pin "1") (pinfunction "1_1") (pintype "passive"))
      (node (ref "U1") (pin "2") (pinfunction "AOUT1_2") (pintype "output"))
    )
    (net (code "52") (name "/MotorB+") (class "Default")
      (node (ref "J9") (pin "2") (pinfunction "2_2") (pintype "passive"))
      (node (ref "U1") (pin "7") (pinfunction "BOUT1_7") (pintype "output"))
    )
    (net (code "53") (name "/MotorB-") (class "Default")
      (node (ref "J9") (pin "1") (pinfunction "1_1") (pintype "passive"))
      (node (ref "U1") (pin "5") (pinfunction "BOUT2_5") (pintype "output"))
    )
    (net (code "54") (name "/NR") (class "Default")
      (node (ref "C9") (pin "2") (pinfunction "2_2") (pintype "passive"))
      (node (ref "U15") (pin "4") (pinfunction "NR_4") (pintype "passive"))
    )
    (net (code "55") (name "/PWM0") (class "Default")
      (node (ref "J1") (pin "1") (pinfunction "1_1") (pintype "passive"))
      (node (ref "RN2") (pin "1") (pinfunction "6_1") (pintype "passive"))
    )
    (net (code "56") (name "/PWM1") (class "Default")
      (node (ref "J1") (pin "2") (pinfunction "2_2") (pintype "passive"))
      (node (ref "RN2") (pin "2") (pinfunction "2_2") (pintype "passive"))
    )
    (net (code "57") (name "/PWM2") (class "Default")
      (node (ref "J1") (pin "3") (pinfunction "3_3") (pintype "passive"))
      (node (ref "RN2") (pin "3") (pinfunction "3_3") (pintype "passive"))
    )
    (net (code "58") (name "/PWM3") (class "Default")
      (node (ref "J1") (pin "4") (pinfunction "4_4") (pintype "passive"))
      (node (ref "RN2") (pin "4") (pinfunction "4_4") (pintype "passive"))
    )
    (net (code "59") (name "/PWM4") (class "Default")
      (node (ref "J7") (pin "1") (pinfunction "1_1") (pintype "passive"))
      (node (ref "RN3") (pin "1") (pinfunction "6_1") (pintype "passive"))
    )
    (net (code "60") (name "/PWM5") (class "Default")
      (node (ref "J7") (pin "2") (pinfunction "2_2") (pintype "passive"))
      (node (ref "RN3") (pin "2") (pinfunction "2_2") (pintype "passive"))
    )
    (net (code "61") (name "/PWM6") (class "Default")
      (node (ref "J7") (pin "3") (pinfunction "3_3") (pintype "passive"))
      (node (ref "RN3") (pin "3") (pinfunction "3_3") (pintype "passive"))
    )
    (net (code "62") (name "/PWM7") (class "Default")
      (node (ref "J7") (pin "4") (pinfunction "4_4") (pintype "passive"))
      (node (ref "RN3") (pin "4") (pinfunction "4_4") (pintype "passive"))
    )
    (net (code "67") (name "/PWM12") (class "Default")
      (node (ref "RN4") (pin "1") (pinfunction "6_1") (pintype "passive"))
      (node (ref "U1") (pin "16") (pinfunction "AIN1_16") (pintype "input"))
    )
    (net (code "68") (name "/PWM13") (class "Default")
      (node (ref "RN4") (pin "2") (pinfunction "2_2") (pintype "passive"))
      (node (ref "U1") (pin "15") (pinfunction "AIN2_15") (pintype "input"))
    )
    (net (code "69") (name "/PWM14") (class "Default")
      (node (ref "RN4") (pin "3") (pinfunction "3_3") (pintype "passive"))
      (node (ref "U1") (pin "10") (pinfunction "BIN2_10") (pintype "input"))
    )
    (net (code "70") (name "/PWM15") (class "Default")
      (node (ref "RN4") (pin "4") (pinfunction "4_4") (pintype "passive"))
      (node (ref "U1") (pin "9") (pinfunction "BIN1_9") (pintype "input"))
    )
    (net (code "71") (name "/SW") (class "Default")
      (node (ref "D1") (pin "1") (pinfunction "K_1") (pintype "passive"))
      (node (ref "L1") (pin "1") (pinfunction "1_1") (pintype "passive"))
      (node (ref "U3") (pin "2") (pinfunction "OUT_2") (pintype "power_in"))
    )
    (net (code "72") (name "3.3V") (class "Default")
      (node (ref "J2") (pin "1") (pintype "passive"))
      (node (ref "J2") (pin "17") (pintype "passive"))
      (node (ref "S2") (pin "3") (pinfunction "3_3") (pintype "passive"))
    )
    (net (code "73") (name "5V") (class "Default")
      (node (ref "C11") (pin "1") (pinfunction "1_1") (pintype "passive"))
      (node (ref "C15") (pin "1") (pinfunction "1_1") (pintype "passive"))
      (node (ref "C8") (pin "1") (pinfunction "1_1") (pintype "passive"))
      (node (ref "J1") (pin "5") (pinfunction "5_5") (pintype "passive"))
      (node (ref "J1") (pin "6") (pinfunction "6_6") (pintype "passive"))
      (node (ref "J1") (pin "7") (pinfunction "7_7") (pintype "passive"))
      (node (ref "J1") (pin "8") (pinfunction "8_8") (pintype "passive"))
      (node (ref "J2") (pin "2") (pintype "passive"))
      (node (ref "J2") (pin "4") (pintype "passive"))
      (node (ref "J3") (pin "1") (pinfunction "1_1") (pintype "passive"))
      (node (ref "J4") (pin "1") (pinfunction "1_1") (pintype "passive"))
      (node (ref "J5") (pin "1") (pinfunction "1_1") (pintype "passive"))
      (node (ref "J6") (pin "1") (pinfunction "1_1") (pintype "passive"))
      (node (ref "J7") (pin "5") (pinfunction "5_5") (pintype "passive"))
      (node (ref "J7") (pin "6") (pinfunction "6_6") (pintype "passive"))
      (node (ref "J7") (pin "7") (pinfunction "7_7") (pintype "passive"))
      (node (ref "J7") (pin "8") (pinfunction "8_8") (pintype "passive"))
      (node (ref "J8") (pin "1") (pinfunction "1_1") (pintype "passive"))
      (node (ref "L1") (pin "2") (pinfunction "2_2") (pintype "passive"))
      (node (ref "R1") (pin "1") (pinfunction "1_1") (pintype "passive"))
      (node (ref "R5") (pin "2") (pinfunction "2_2") (pintype "passive"))
      (node (ref "U12") (pin "28") (pinfunction "VDD_28") (pintype "power_in"))
      (node (ref "U15") (pin "1") (pinfunction "IN_1") (pintype "power_in"))
      (node (ref "U15") (pin "3") (pinfunction "EN_3") (pintype "input"))
      (node (ref "U18") (pin "15") (pinfunction "VREF_15") (pintype "input"))
      (node (ref "U18") (pin "16") (pinfunction "VDD_16") (pintype "power_in"))
      (node (ref "VR1") (pin "1") (pinfunction "CCW_1") (pintype "passive"))
      (node (ref "VR2") (pin "1") (pinfunction "CCW_1") (pintype "passive"))
    )
    (net (code "74") (name "B+SW") (class "Default")
      (node (ref "C1") (pin "1") (pinfunction "1_1") (pintype "passive"))
      (node (ref "C16") (pin "1") (pinfunction "1_1") (pintype "passive"))
      (node (ref "C17") (pin "1") (pinfunction "1_1") (pintype "passive"))
      (node (ref "C2") (pin "1") (pinfunction "1_1") (pintype "passive"))
      (node (ref "LED1") (pin "2") (pinfunction "A_2") (pintype "passive"))
      (node (ref "LED2") (pin "2") (pinfunction "A_2") (pintype "passive"))
      (node (ref "LED3") (pin "2") (pinfunction "A_2") (pintype "passive"))
      (node (ref "LED4") (pin "2") (pinfunction "A_2") (pintype "passive"))
      (node (ref "R3") (pin "2") (pinfunction "2_2") (pintype "passive"))
      (node (ref "R4") (pin "2") (pinfunction "2_2") (pintype "passive"))
      (node (ref "S1") (pin "1") (pinfunction "1_1") (pintype "passive"))
      (node (ref "U1") (pin "1") (pinfunction "~{SLEEP}_1") (pintype "input"))
      (node (ref "U1") (pin "12") (pinfunction "VM_12") (pintype "power_in"))
      (node (ref "U2") (pin "2") (pinfunction "VCC+_2") (pintype "power_in"))
      (node (ref "U3") (pin "1") (pinfunction "VIN_1") (pintype "power_in"))
    )
    (net (code "75") (name "GND") (class "Default")
      (node (ref "C1") (pin "2") (pinfunction "2_2") (pintype "passive"))
      (node (ref "C10") (pin "2") (pinfunction "2_2") (pintype "passive"))
      (node (ref "C11") (pin "2") (pinfunction "2_2") (pintype "passive"))
      (node (ref "C12") (pin "2") (pinfunction "2_2") (pintype "passive"))
      (node (ref "C13") (pin "2") (pinfunction "2_2") (pintype "passive"))
      (node (ref "C14") (pin "1") (pinfunction "1_1") (pintype "passive"))
      (node (ref "C15") (pin "2") (pinfunction "2_2") (pintype "passive"))
      (node (ref "C16") (pin "2") (pinfunction "2_2") (pintype "passive"))
      (node (ref "C17") (pin "2") (pinfunction "2_2") (pintype "passive"))
      (node (ref "C2") (pin "2") (pinfunction "2_2") (pintype "passive"))
      (node (ref "C3") (pin "1") (pinfunction "1_1") (pintype "passive"))
      (node (ref "C8") (pin "2") (pinfunction "2_2") (pintype "passive"))
      (node (ref "C9") (pin "1") (pinfunction "1_1") (pintype "passive"))
      (node (ref "D1") (pin "2") (pinfunction "A_2") (pintype "passive"))
      (node (ref "J1") (pin "10") (pinfunction "10_10") (pintype "passive"))
      (node (ref "J1") (pin "11") (pinfunction "11_11") (pintype "passive"))
      (node (ref "J1") (pin "12") (pinfunction "12_12") (pintype "passive"))
      (node (ref "J1") (pin "9") (pinfunction "9_9") (pintype "passive"))
      (node (ref "J10") (pin "3") (pinfunction "MNT_1_3") (pintype "passive"))
      (node (ref "J10") (pin "4") (pinfunction "MNT_2_4") (pintype "passive"))
      (node (ref "J11") (pin "2") (pinfunction "2_2") (pintype "passive"))
      (node (ref "J11") (pin "3") (pinfunction "MNT_1_3") (pintype "passive"))
      (node (ref "J11") (pin "4") (pinfunction "MNT_2_4") (pintype "passive"))
      (node (ref "J2") (pin "14") (pintype "passive"))
      (node (ref "J2") (pin "20") (pintype "passive"))
      (node (ref "J2") (pin "25") (pintype "passive"))
      (node (ref "J2") (pin "30") (pintype "passive"))
      (node (ref "J2") (pin "34") (pintype "passive"))
      (node (ref "J2") (pin "39") (pintype "passive"))
      (node (ref "J2") (pin "6") (pintype "passive"))
      (node (ref "J2") (pin "9") (pintype "passive"))
      (node (ref "J3") (pin "4") (pinfunction "4_4") (pintype "passive"))
      (node (ref "J3") (pin "5") (pinfunction "MNT_1_5") (pintype "passive"))
      (node (ref "J3") (pin "6") (pinfunction "MNT_2_6") (pintype "passive"))
      (node (ref "J4") (pin "4") (pinfunction "4_4") (pintype "passive"))
      (node (ref "J4") (pin "5") (pinfunction "MNT_1_5") (pintype "passive"))
      (node (ref "J4") (pin "6") (pinfunction "MNT_2_6") (pintype "passive"))
      (node (ref "J5") (pin "4") (pinfunction "4_4") (pintype "passive"))
      (node (ref "J5") (pin "5") (pinfunction "MNT_1_5") (pintype "passive"))
      (node (ref "J5") (pin "6") (pinfunction "MNT_2_6") (pintype "passive"))
      (node (ref "J6") (pin "4") (pinfunction "4_4") (pintype "passive"))
      (node (ref "J6") (pin "5") (pinfunction "MNT_1_5") (pintype "passive"))
      (node (ref "J6") (pin "6") (pinfunction "MNT_2_6") (pintype "passive"))
      (node (ref "J7") (pin "10") (pinfunction "10_10") (pintype "passive"))
      (node (ref "J7") (pin "11") (pinfunction "11_11") (pintype "passive"))
      (node (ref "J7") (pin "12") (pinfunction "12_12") (pintype "passive"))
      (node (ref "J7") (pin "9") (pinfunction "9_9") (pintype "passive"))
      (node (ref "J8") (pin "4") (pinfunction "4_4") (pintype "passive"))
      (node (ref "J8") (pin "5") (pinfunction "MNT_1_5") (pintype "passive"))
      (node (ref "J8") (pin "6") (pinfunction "MNT_2_6") (pintype "passive"))
      (node (ref "J9") (pin "3") (pinfunction "MNT_1_3") (pintype "passive"))
      (node (ref "J9") (pin "4") (pinfunction "MNT_2_4") (pintype "passive"))
      (node (ref "LED5") (pin "1") (pinfunction "K_1") (pintype "passive"))
      (node (ref "PTH1") (pin "0") (pinfunction "0_0") (pintype "passive"))
      (node (ref "PTH2") (pin "0") (pinfunction "0_0") (pintype "passive"))
      (node (ref "PTH3") (pin "0") (pinfunction "0_0") (pintype "passive"))
      (node (ref "PTH4") (pin "0") (pinfunction "0_0") (pintype "passive"))
      (node (ref "R10") (pin "1") (pinfunction "1_1") (pintype "passive"))
      (node (ref "R11") (pin "1") (pinfunction "1_1") (pintype "passive"))
      (node (ref "R12") (pin "1") (pinfunction "1_1") (pintype "passive"))
      (node (ref "R13") (pin "2") (pinfunction "2_2") (pintype "passive"))
      (node (ref "R24") (pin "1") (pinfunction "1_1") (pintype "passive"))
      (node (ref "S2") (pin "1") (pinfunction "1_1") (pintype "passive"))
      (node (ref "U1") (pin "13") (pinfunction "GND_13") (pintype "power_in"))
      (node (ref "U1") (pin "17") (pinfunction "EXP_17") (pintype "power_in"))
      (node (ref "U1") (pin "3") (pinfunction "AISEN_3") (pintype "passive"))
      (node (ref "U1") (pin "6") (pinfunction "BISEN_6") (pintype "passive"))
      (node (ref "U12") (pin "1") (pinfunction "A0_1") (pintype "input"))
      (node (ref "U12") (pin "14") (pinfunction "VSS_14") (pintype "power_in"))
      (node (ref "U12") (pin "2") (pinfunction "A1_2") (pintype "input"))
      (node (ref "U12") (pin "23") (pinfunction "~{OE}_23") (pintype "input"))
      (node (ref "U12") (pin "24") (pinfunction "A5_24") (pintype "input"))
      (node (ref "U12") (pin "25") (pinfunction "EXTCLK_25") (pintype "input"))
      (node (ref "U12") (pin "3") (pinfunction "A2_3") (pintype "input"))
      (node (ref "U12") (pin "4") (pinfunction "A3_4") (pintype "input"))
      (node (ref "U12") (pin "5") (pinfunction "A4_5") (pintype "input"))
      (node (ref "U14") (pin "11") (pinfunction "FSYNC_11") (pintype "passive"))
      (node (ref "U14") (pin "18") (pinfunction "GND_18") (pintype "passive"))
      (node (ref "U14") (pin "20") (pinfunction "RESV_2_20") (pintype "passive"))
      (node (ref "U14") (pin "25") (pinfunction "EP_25") (pintype "passive"))
      (node (ref "U14") (pin "9") (pinfunction "SDO/ADO_9") (pintype "passive"))
      (node (ref "U15") (pin "2") (pinfunction "GND_2") (pintype "power_in"))
      (node (ref "U18") (pin "14") (pinfunction "AGND_14") (pintype "power_in"))
      (node (ref "U18") (pin "9") (pinfunction "DGND_9") (pintype "power_in"))
      (node (ref "U2") (pin "11") (pinfunction "VCC-_11") (pintype "power_in"))
      (node (ref "U2") (pin "17") (pinfunction "NC_17") (pintype "passive"))
      (node (ref "U3") (pin "3") (pinfunction "GND_3") (pintype "power_in"))
      (node (ref "U3") (pin "5") (pinfunction "~{ON}/OFF_5") (pintype "input"))
      (node (ref "U3") (pin "6") (pinfunction "TAB_6") (pintype "power_in"))
      (node (ref "U8") (pin "3") (pinfunction "A_3") (pintype "passive"))
    )
    (net (code "76") (name "Net-(LED1-K)") (class "Default")
      (node (ref "LED1") (pin "1") (pinfunction "K_1") (pintype "passive"))
      (node (ref "RN1") (pin "5") (pinfunction "5_5") (pintype "passive"))
    )
    (net (code "77") (name "Net-(LED2-K)") (class "Default")
      (node (ref "LED2") (pin "1") (pinfunction "K_1") (pintype "passive"))
      (node (ref "RN1") (pin "6") (pinfunction "6_6") (pintype "passive"))
    )
    (net (code "78") (name "Net-(LED3-K)") (class "Default")
      (node (ref "LED3") (pin "1") (pinfunction "K_1") (pintype "passive"))
      (node (ref "RN1") (pin "7") (pinfunction "7_7") (pintype "passive"))
    )
    (net (code "79") (name "Net-(LED4-K)") (class "Default")
      (node (ref "LED4") (pin "1") (pinfunction "K_1") (pintype "passive"))
      (node (ref "RN1") (pin "8") (pinfunction "8_8") (pintype "passive"))
    )
    (net (code "80") (name "Net-(LED5-A)") (class "Default")
      (node (ref "LED5") (pin "2") (pinfunction "A_2") (pintype "passive"))
      (node (ref "R5") (pin "1") (pinfunction "1_1") (pintype "passive"))
    )
    (net (code "81") (name "Net-(R16-Pad2)") (class "Default")
      (node (ref "R16") (pin "2") (pinfunction "2_2") (pintype "passive"))
      (node (ref "S2") (pin "2") (pinfunction "2_2") (pintype "passive"))
    )
    (net (code "82") (name "Net-(U8-C)") (class "Default")
      (node (ref "R4") (pin "1") (pinfunction "1_1") (pintype "passive"))
      (node (ref "R6") (pin "1") (pinfunction "1_1") (pintype "passive"))
      (node (ref "U8") (pin "1") (pinfunction "C_1") (pintype "passive"))
      (node (ref "U8") (pin "2") (pinfunction "REF_2") (pintype "passive"))
    )
    (net (code "83") (name "Net-(U12-LED0)") (class "Default")
      (node (ref "RN2") (pin "8") (pinfunction "8_8") (pintype "passive"))
      (node (ref "U12") (pin "6") (pinfunction "LED0_6") (pintype "passive"))
    )
    (net (code "84") (name "Net-(U12-LED1)") (class "Default")
      (node (ref "RN2") (pin "7") (pinfunction "7_7") (pintype "passive"))
      (node (ref "U12") (pin "7") (pinfunction "LED1_7") (pintype "passive"))
    )
    (net (code "85") (name "Net-(U12-LED2)") (class "Default")
      (node (ref "RN2") (pin "6") (pinfunction "6_6") (pintype "passive"))
      (node (ref "U12") (pin "8") (pinfunction "LED2_8") (pintype "passive"))
    )
    (net (code "86") (name "Net-(U12-LED3)") (class "Default")
      (node (ref "RN2") (pin "5") (pinfunction "5_5") (pintype "passive"))
      (node (ref "U12") (pin "9") (pinfunction "LED3_9") (pintype "passive"))
    )
    (net (code "87") (name "Net-(U12-LED4)") (class "Default")
      (node (ref "RN3") (pin "8") (pinfunction "8_8") (pintype "passive"))
      (node (ref "U12") (pin "10") (pinfunction "LED4_10") (pintype "passive"))
    )
    (net (code "88") (name "Net-(U12-LED5)") (class "Default")
      (node (ref "RN3") (pin "7") (pinfunction "7_7") (pintype "passive"))
      (node (ref "U12") (pin "11") (pinfunction "LED5_11") (pintype "passive"))
    )
    (net (code "89") (name "Net-(U12-LED6)") (class "Default")
      (node (ref "RN3") (pin "6") (pinfunction "6_6") (pintype "passive"))
      (node (ref "U12") (pin "12") (pinfunction "LED6_12") (pintype "passive"))
    )
    (net (code "90") (name "Net-(U12-LED7)") (class "Default")
      (node (ref "RN3") (pin "5") (pinfunction "5_5") (pintype "passive"))
      (node (ref "U12") (pin "13") (pinfunction "LED7_13") (pintype "passive"))
    )
    (net (code "91") (name "Net-(U12-LED12)") (class "Default")
      (node (ref "RN4") (pin "8") (pinfunction "8_8") (pintype "passive"))
      (node (ref "U12") (pin "19") (pinfunction "LED12_19") (pintype "passive"))
    )
    (net (code "92") (name "Net-(U12-LED13)") (class "Default")
      (node (ref "RN4") (pin "7") (pinfunction "7_7") (pintype "passive"))
      (node (ref "U12") (pin "20") (pinfunction "LED13_20") (pintype "passive"))
    )
    (net (code "93") (name "Net-(U12-LED14)") (class "Default")
      (node (ref "RN4") (pin "6") (pinfunction "6_6") (pintype "passive"))
      (node (ref "U12") (pin "21") (pinfunction "LED14_21") (pintype "passive"))
    )
    (net (code "94") (name "Net-(U12-LED15)") (class "Default")
      (node (ref "RN4") (pin "5") (pinfunction "5_5") (pintype "passive"))
      (node (ref "U12") (pin "22") (pinfunction "LED15_22") (pintype "passive"))
    )
    (net (code "95") (name "Net-(U14-REGOUT)") (class "Default")
      (node (ref "C13") (pin "1") (pinfunction "1_1") (pintype "passive"))
      (node (ref "U14") (pin "10") (pinfunction "REGOUT_10") (pintype "passive"))
    )
    (net (code "96") (name "unconnected-(U1-NC-Pad11)") (class "Default")
      (node (ref "U1") (pin "11") (pinfunction "NC_11") (pintype "passive+no_connect"))
    )
    (net (code "97") (name "unconnected-(U1-NC-Pad14)") (class "Default")
      (node (ref "U1") (pin "14") (pinfunction "NC_14") (pintype "passive+no_connect"))
    )
    (net (code "98") (name "unconnected-(U1-~{FAULT}-Pad8)") (class "Default")
      (node (ref "U1") (pin "8") (pinfunction "~{FAULT}_8") (pintype "output+no_connect"))
    )
    (net (code "99") (name "unconnected-(U2-NC-Pad3)") (class "Default")
      (node (ref "U2") (pin "3") (pinfunction "NC_3") (pintype "passive+no_connect"))
    )
    (net (code "100") (name "unconnected-(U2-NC-Pad10)") (class "Default")
      (node (ref "U2") (pin "10") (pinfunction "NC_10") (pintype "passive+no_connect"))
    )
    (net (code "101") (name "unconnected-(U12-LED8-Pad15)") (class "Default")
      (node (ref "U12") (pin "15") (pinfunction "LED8_15") (pintype "passive+no_connect"))
    )
    (net (code "102") (name "unconnected-(U12-LED9-Pad16)") (class "Default")
      (node (ref "U12") (pin "16") (pinfunction "LED9_16") (pintype "passive+no_connect"))
    )
    (net (code "103") (name "unconnected-(U12-LED10-Pad17)") (class "Default")
      (node (ref "U12") (pin "17") (pinfunction "LED10_17") (pintype "passive+no_connect"))
    )
    (net (code "104") (name "unconnected-(U12-LED11-Pad18)") (class "Default")
      (node (ref "U12") (pin "18") (pinfunction "LED11_18") (pintype "passive+no_connect"))
    )
    (net (code "105") (name "unconnected-(U14-AUX_CL-Pad7)") (class "Default")
      (node (ref "U14") (pin "7") (pinfunction "AUX_CL_7") (pintype "passive+no_connect"))
    )
    (net (code "106") (name "unconnected-(U14-AUX_DA-Pad21)") (class "Default")
      (node (ref "U14") (pin "21") (pinfunction "AUX_DA_21") (pintype "passive+no_connect"))
    )
    (net (code "107") (name "unconnected-(U14-INT1-Pad12)") (class "Default")
      (node (ref "U14") (pin "12") (pinfunction "INT1_12") (pintype "passive+no_connect"))
    )
    (net (code "108") (name "unconnected-(U14-NC_1-Pad1)") (class "Default")
      (node (ref "U14") (pin "1") (pinfunction "NC_1_1") (pintype "passive+no_connect"))
    )
    (net (code "109") (name "unconnected-(U14-NC_2-Pad2)") (class "Default")
      (node (ref "U14") (pin "2") (pinfunction "NC_2_2") (pintype "passive+no_connect"))
    )
    (net (code "110") (name "unconnected-(U14-NC_3-Pad3)") (class "Default")
      (node (ref "U14") (pin "3") (pinfunction "NC_3_3") (pintype "passive+no_connect"))
    )
    (net (code "111") (name "unconnected-(U14-NC_4-Pad4)") (class "Default")
      (node (ref "U14") (pin "4") (pinfunction "NC_4_4") (pintype "passive+no_connect"))
    )
    (net (code "112") (name "unconnected-(U14-NC_5-Pad5)") (class "Default")
      (node (ref "U14") (pin "5") (pinfunction "NC_5_5") (pintype "passive+no_connect"))
    )
    (net (code "113") (name "unconnected-(U14-NC_6-Pad6)") (class "Default")
      (node (ref "U14") (pin "6") (pinfunction "NC_6_6") (pintype "passive+no_connect"))
    )
    (net (code "114") (name "unconnected-(U14-NC_7-Pad14)") (class "Default")
      (node (ref "U14") (pin "14") (pinfunction "NC_7_14") (pintype "passive+no_connect"))
    )
    (net (code "115") (name "unconnected-(U14-NC_8-Pad15)") (class "Default")
      (node (ref "U14") (pin "15") (pinfunction "NC_8_15") (pintype "passive+no_connect"))
    )
    (net (code "116") (name "unconnected-(U14-NC_9-Pad16)") (class "Default")
      (node (ref "U14") (pin "16") (pinfunction "NC_9_16") (pintype "passive+no_connect"))
    )
    (net (code "117") (name "unconnected-(U14-NC_10-Pad17)") (class "Default")
      (node (ref "U14") (pin "17") (pinfunction "NC_10_17") (pintype "passive+no_connect"))
    )
    (net (code "118") (name "unconnected-(U14-RESV_1-Pad19)") (class "Default")
      (node (ref "U14") (pin "19") (pinfunction "RESV_1_19") (pintype "passive+no_connect"))
    )
    (net (code "119") (name "unconnected-(VR1-CW-Pad3)") (class "Default")
      (node (ref "VR1") (pin "3") (pinfunction "CW_3") (pintype "passive+no_connect"))
    )
    (net (code "120") (name "unconnected-(VR2-CW-Pad3)") (class "Default")
      (node (ref "VR2") (pin "3") (pinfunction "CW_3") (pintype "passive+no_connect"))
    )
  )
)
